# BitReceptor.net
KiCad netlist of a schematic drawn in EAGLE
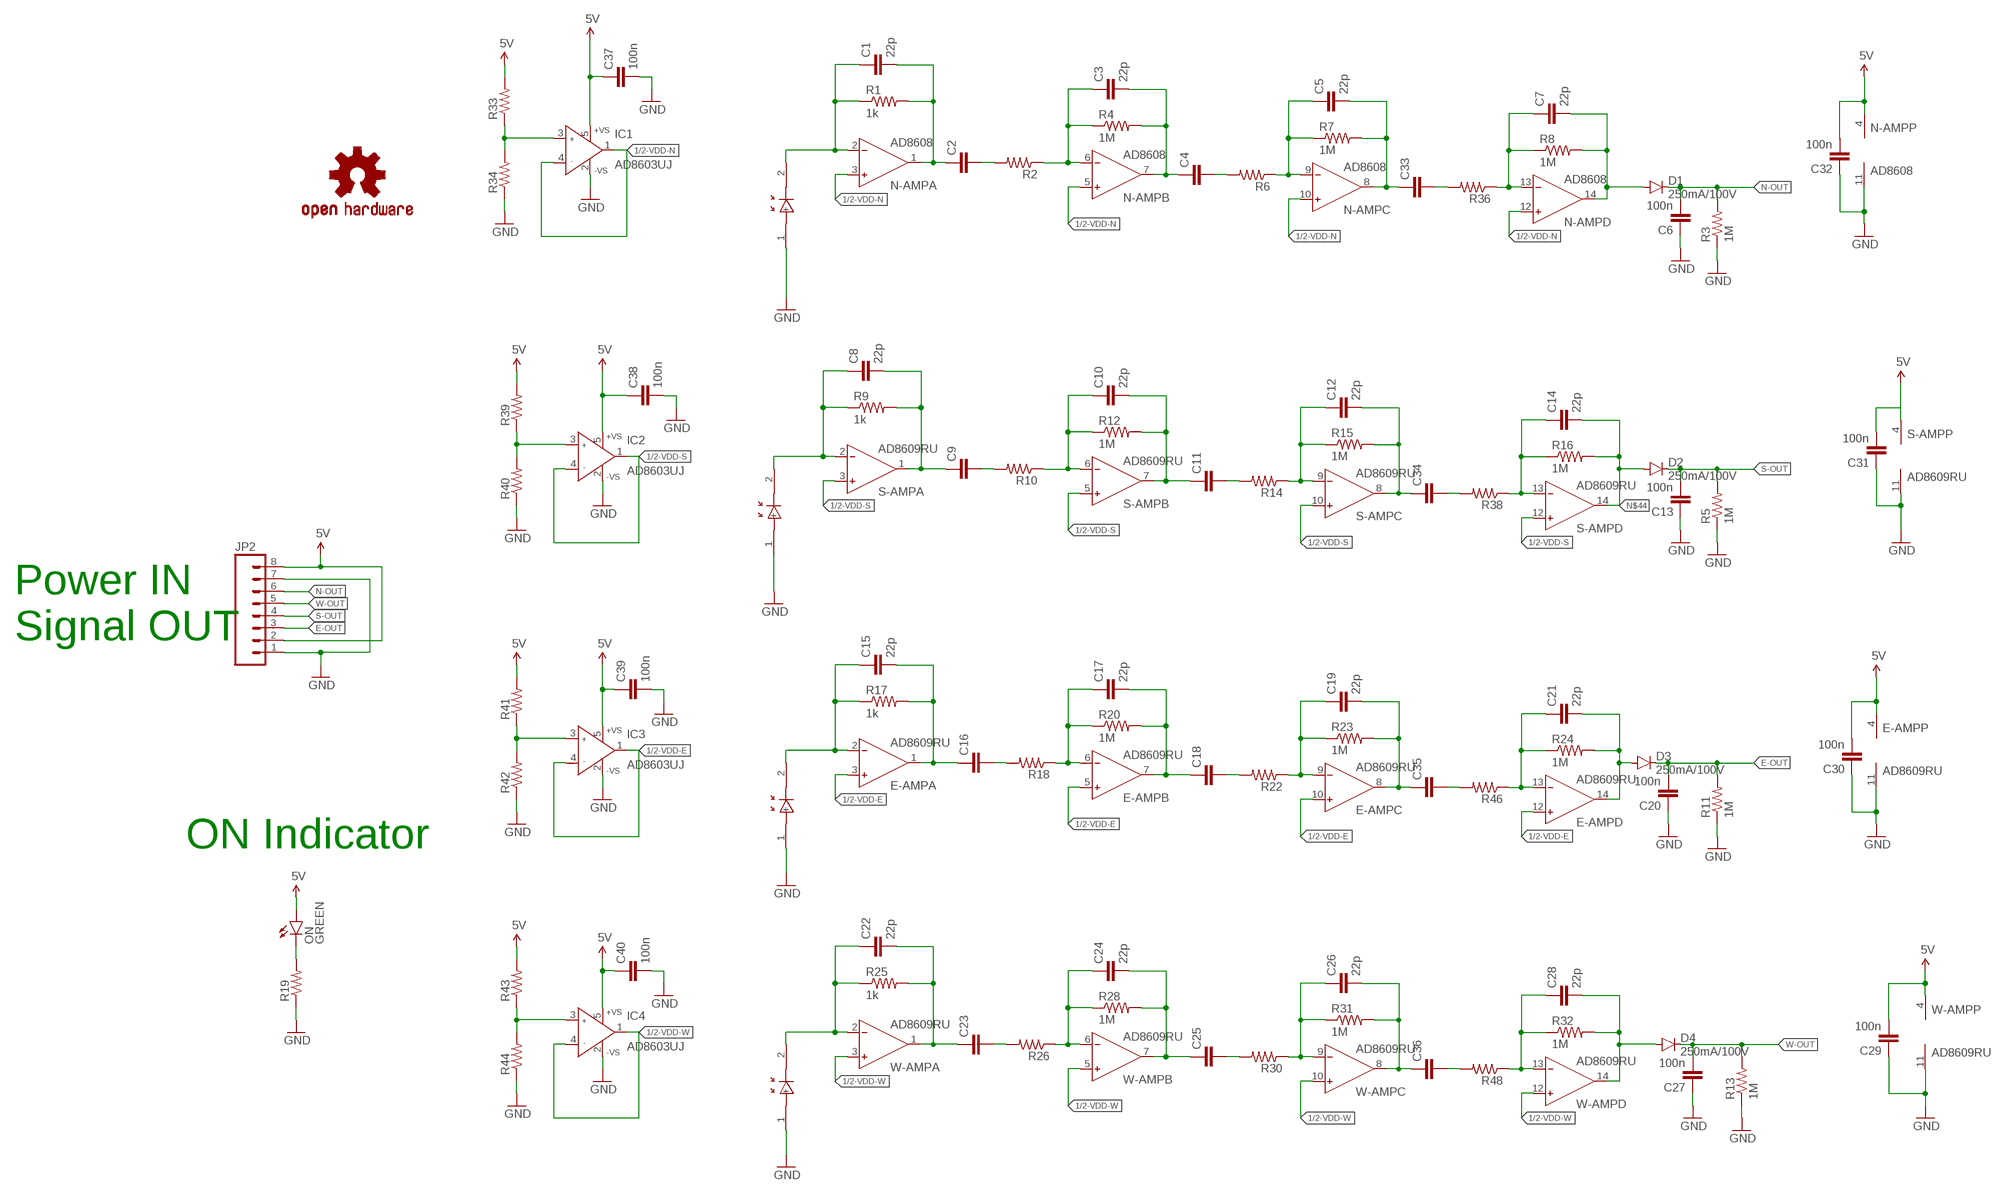
[diagram p0: schematic, sheet 1]

(export (version "E")
  (design (tool "Eeschema 10.0.6"))
  (components
    (comp (ref "C1")
      (value "22p")
      (footprint "eagle-import:C0402")
      (libsource (lib "eagle-import") (part "C-EUC0402"))
    )
    (comp (ref "C2")
      (value "C-EUC0402")
      (footprint "eagle-import:C0402")
      (libsource (lib "eagle-import") (part "C-EUC0402"))
    )
    (comp (ref "C3")
      (value "22p")
      (footprint "eagle-import:C0402")
      (libsource (lib "eagle-import") (part "C-EUC0402"))
    )
    (comp (ref "C4")
      (value "C-EUC0402")
      (footprint "eagle-import:C0402")
      (libsource (lib "eagle-import") (part "C-EUC0402"))
    )
    (comp (ref "C5")
      (value "22p")
      (footprint "eagle-import:C0402")
      (libsource (lib "eagle-import") (part "C-EUC0402"))
    )
    (comp (ref "C6")
      (value "100n")
      (footprint "eagle-import:C0402")
      (libsource (lib "eagle-import") (part "C-EUC0402"))
    )
    (comp (ref "C7")
      (value "22p")
      (footprint "eagle-import:C0402")
      (libsource (lib "eagle-import") (part "C-EUC0402"))
    )
    (comp (ref "C8")
      (value "22p")
      (footprint "eagle-import:C0402")
      (libsource (lib "eagle-import") (part "C-EUC0402"))
    )
    (comp (ref "C9")
      (value "C-EUC0402")
      (footprint "eagle-import:C0402")
      (libsource (lib "eagle-import") (part "C-EUC0402"))
    )
    (comp (ref "C10")
      (value "22p")
      (footprint "eagle-import:C0402")
      (libsource (lib "eagle-import") (part "C-EUC0402"))
    )
    (comp (ref "C11")
      (value "C-EUC0402")
      (footprint "eagle-import:C0402")
      (libsource (lib "eagle-import") (part "C-EUC0402"))
    )
    (comp (ref "C12")
      (value "22p")
      (footprint "eagle-import:C0402")
      (libsource (lib "eagle-import") (part "C-EUC0402"))
    )
    (comp (ref "C13")
      (value "100n")
      (footprint "eagle-import:C0402")
      (libsource (lib "eagle-import") (part "C-EUC0402"))
    )
    (comp (ref "C14")
      (value "22p")
      (footprint "eagle-import:C0402")
      (libsource (lib "eagle-import") (part "C-EUC0402"))
    )
    (comp (ref "C15")
      (value "22p")
      (footprint "eagle-import:C0402")
      (libsource (lib "eagle-import") (part "C-EUC0402"))
    )
    (comp (ref "C16")
      (value "C-EUC0402")
      (footprint "eagle-import:C0402")
      (libsource (lib "eagle-import") (part "C-EUC0402"))
    )
    (comp (ref "C17")
      (value "22p")
      (footprint "eagle-import:C0402")
      (libsource (lib "eagle-import") (part "C-EUC0402"))
    )
    (comp (ref "C18")
      (value "C-EUC0402")
      (footprint "eagle-import:C0402")
      (libsource (lib "eagle-import") (part "C-EUC0402"))
    )
    (comp (ref "C19")
      (value "22p")
      (footprint "eagle-import:C0402")
      (libsource (lib "eagle-import") (part "C-EUC0402"))
    )
    (comp (ref "C20")
      (value "100n")
      (footprint "eagle-import:C0402")
      (libsource (lib "eagle-import") (part "C-EUC0402"))
    )
    (comp (ref "C21")
      (value "22p")
      (footprint "eagle-import:C0402")
      (libsource (lib "eagle-import") (part "C-EUC0402"))
    )
    (comp (ref "C22")
      (value "22p")
      (footprint "eagle-import:C0402")
      (libsource (lib "eagle-import") (part "C-EUC0402"))
    )
    (comp (ref "C23")
      (value "C-EUC0402")
      (footprint "eagle-import:C0402")
      (libsource (lib "eagle-import") (part "C-EUC0402"))
    )
    (comp (ref "C24")
      (value "22p")
      (footprint "eagle-import:C0402")
      (libsource (lib "eagle-import") (part "C-EUC0402"))
    )
    (comp (ref "C25")
      (value "C-EUC0402")
      (footprint "eagle-import:C0402")
      (libsource (lib "eagle-import") (part "C-EUC0402"))
    )
    (comp (ref "C26")
      (value "22p")
      (footprint "eagle-import:C0402")
      (libsource (lib "eagle-import") (part "C-EUC0402"))
    )
    (comp (ref "C27")
      (value "100n")
      (footprint "eagle-import:C0402")
      (libsource (lib "eagle-import") (part "C-EUC0402"))
    )
    (comp (ref "C28")
      (value "22p")
      (footprint "eagle-import:C0402")
      (libsource (lib "eagle-import") (part "C-EUC0402"))
    )
    (comp (ref "C29")
      (value "100n")
      (footprint "eagle-import:C0402")
      (libsource (lib "eagle-import") (part "C-EUC0402"))
    )
    (comp (ref "C30")
      (value "100n")
      (footprint "eagle-import:C0402")
      (libsource (lib "eagle-import") (part "C-EUC0402"))
    )
    (comp (ref "C31")
      (value "100n")
      (footprint "eagle-import:C0402")
      (libsource (lib "eagle-import") (part "C-EUC0402"))
    )
    (comp (ref "C32")
      (value "100n")
      (footprint "eagle-import:C0402")
      (libsource (lib "eagle-import") (part "C-EUC0402"))
    )
    (comp (ref "C33")
      (value "C-EUC0402")
      (footprint "eagle-import:C0402")
      (libsource (lib "eagle-import") (part "C-EUC0402"))
    )
    (comp (ref "C34")
      (value "C-EUC0402")
      (footprint "eagle-import:C0402")
      (libsource (lib "eagle-import") (part "C-EUC0402"))
    )
    (comp (ref "C35")
      (value "C-EUC0402")
      (footprint "eagle-import:C0402")
      (libsource (lib "eagle-import") (part "C-EUC0402"))
    )
    (comp (ref "C36")
      (value "C-EUC0402")
      (footprint "eagle-import:C0402")
      (libsource (lib "eagle-import") (part "C-EUC0402"))
    )
    (comp (ref "C37")
      (value "100n")
      (footprint "eagle-import:C0402")
      (libsource (lib "eagle-import") (part "C-EUC0402"))
    )
    (comp (ref "C38")
      (value "100n")
      (footprint "eagle-import:C0402")
      (libsource (lib "eagle-import") (part "C-EUC0402"))
    )
    (comp (ref "C39")
      (value "100n")
      (footprint "eagle-import:C0402")
      (libsource (lib "eagle-import") (part "C-EUC0402"))
    )
    (comp (ref "C40")
      (value "100n")
      (footprint "eagle-import:C0402")
      (libsource (lib "eagle-import") (part "C-EUC0402"))
    )
    (comp (ref "D1")
      (value "250mA/100V")
      (footprint "eagle-import:SOD-323")
      (libsource (lib "eagle-import") (part "DIODEBAS16"))
    )
    (comp (ref "D2")
      (value "250mA/100V")
      (footprint "eagle-import:SOD-323")
      (libsource (lib "eagle-import") (part "DIODEBAS16"))
    )
    (comp (ref "D3")
      (value "250mA/100V")
      (footprint "eagle-import:SOD-323")
      (libsource (lib "eagle-import") (part "DIODEBAS16"))
    )
    (comp (ref "D4")
      (value "250mA/100V")
      (footprint "eagle-import:SOD-323")
      (libsource (lib "eagle-import") (part "DIODEBAS16"))
    )
    (comp (ref "E-AMP")
      (value "AD8609RU")
      (footprint "eagle-import:TSSOP14")
      (fields (field (name "MF") "ALTERA CORPORATION") (field (name "MPN") "AD8609ARUZ"))
      (libsource (lib "eagle-import") (part "AD8609RU"))
    )
    (comp (ref "E-PD1")
      (value "BPW46")
      (footprint "eagle-import:PIN-PHOTODIODE")
      (libsource (lib "eagle-import") (part "BPW46"))
    )
    (comp (ref "IC1")
      (value "AD8603UJ")
      (footprint "eagle-import:SOT23-5")
      (fields (field (name "MF") "ALTERA CORPORATION") (field (name "MPN") "AD8603AUJZ-REEL7"))
      (libsource (lib "eagle-import") (part "AD8603UJ"))
    )
    (comp (ref "IC2")
      (value "AD8603UJ")
      (footprint "eagle-import:SOT23-5")
      (fields (field (name "MF") "ALTERA CORPORATION") (field (name "MPN") "AD8603AUJZ-REEL7"))
      (libsource (lib "eagle-import") (part "AD8603UJ"))
    )
    (comp (ref "IC3")
      (value "AD8603UJ")
      (footprint "eagle-import:SOT23-5")
      (fields (field (name "MF") "ALTERA CORPORATION") (field (name "MPN") "AD8603AUJZ-REEL7"))
      (libsource (lib "eagle-import") (part "AD8603UJ"))
    )
    (comp (ref "IC4")
      (value "AD8603UJ")
      (footprint "eagle-import:SOT23-5")
      (fields (field (name "MF") "ALTERA CORPORATION") (field (name "MPN") "AD8603AUJZ-REEL7"))
      (libsource (lib "eagle-import") (part "AD8603UJ"))
    )
    (comp (ref "JP2")
      (value "M08NO_SILK")
      (footprint "eagle-import:1X08_PIN1_NO_SILK")
      (libsource (lib "eagle-import") (part "M08NO_SILK"))
    )
    (comp (ref "LOGO1")
      (value "OSHW-LOGOS")
      (footprint "eagle-import:OSHW-LOGO-S")
      (libsource (lib "eagle-import") (part "OSHW-LOGOS"))
    )
    (comp (ref "N-AMP")
      (value "AD8608")
      (footprint "eagle-import:TSSOP14")
      (fields (field (name "MF") "ALTERA CORPORATION") (field (name "MPN") "AD8609ARUZ"))
      (libsource (lib "eagle-import") (part "AD8609RU"))
    )
    (comp (ref "N-PD1")
      (value "BPW46")
      (footprint "eagle-import:PIN-PHOTODIODE")
      (libsource (lib "eagle-import") (part "BPW46"))
    )
    (comp (ref "ON")
      (value "GREEN")
      (footprint "eagle-import:LED-0603")
      (libsource (lib "eagle-import") (part "LED-GREEN0603"))
    )
    (comp (ref "R1")
      (value "1k")
      (footprint "eagle-import:R0402")
      (libsource (lib "eagle-import") (part "R-US_R0402"))
    )
    (comp (ref "R2")
      (value "R-US_R0402")
      (footprint "eagle-import:R0402")
      (libsource (lib "eagle-import") (part "R-US_R0402"))
    )
    (comp (ref "R3")
      (value "1M")
      (footprint "eagle-import:R0402")
      (libsource (lib "eagle-import") (part "R-US_R0402"))
    )
    (comp (ref "R4")
      (value "1M")
      (footprint "eagle-import:R0402")
      (libsource (lib "eagle-import") (part "R-US_R0402"))
    )
    (comp (ref "R5")
      (value "1M")
      (footprint "eagle-import:R0402")
      (libsource (lib "eagle-import") (part "R-US_R0402"))
    )
    (comp (ref "R6")
      (value "R-US_R0402")
      (footprint "eagle-import:R0402")
      (libsource (lib "eagle-import") (part "R-US_R0402"))
    )
    (comp (ref "R7")
      (value "1M")
      (footprint "eagle-import:R0402")
      (libsource (lib "eagle-import") (part "R-US_R0402"))
    )
    (comp (ref "R8")
      (value "1M")
      (footprint "eagle-import:R0402")
      (libsource (lib "eagle-import") (part "R-US_R0402"))
    )
    (comp (ref "R9")
      (value "1k")
      (footprint "eagle-import:R0402")
      (libsource (lib "eagle-import") (part "R-US_R0402"))
    )
    (comp (ref "R10")
      (value "R-US_R0402")
      (footprint "eagle-import:R0402")
      (libsource (lib "eagle-import") (part "R-US_R0402"))
    )
    (comp (ref "R11")
      (value "1M")
      (footprint "eagle-import:R0402")
      (libsource (lib "eagle-import") (part "R-US_R0402"))
    )
    (comp (ref "R12")
      (value "1M")
      (footprint "eagle-import:R0402")
      (libsource (lib "eagle-import") (part "R-US_R0402"))
    )
    (comp (ref "R13")
      (value "1M")
      (footprint "eagle-import:R0402")
      (libsource (lib "eagle-import") (part "R-US_R0402"))
    )
    (comp (ref "R14")
      (value "R-US_R0402")
      (footprint "eagle-import:R0402")
      (libsource (lib "eagle-import") (part "R-US_R0402"))
    )
    (comp (ref "R15")
      (value "1M")
      (footprint "eagle-import:R0402")
      (libsource (lib "eagle-import") (part "R-US_R0402"))
    )
    (comp (ref "R16")
      (value "1M")
      (footprint "eagle-import:R0402")
      (libsource (lib "eagle-import") (part "R-US_R0402"))
    )
    (comp (ref "R17")
      (value "1k")
      (footprint "eagle-import:R0402")
      (libsource (lib "eagle-import") (part "R-US_R0402"))
    )
    (comp (ref "R18")
      (value "R-US_R0402")
      (footprint "eagle-import:R0402")
      (libsource (lib "eagle-import") (part "R-US_R0402"))
    )
    (comp (ref "R19")
      (value "R-US_R0402")
      (footprint "eagle-import:R0402")
      (libsource (lib "eagle-import") (part "R-US_R0402"))
    )
    (comp (ref "R20")
      (value "1M")
      (footprint "eagle-import:R0402")
      (libsource (lib "eagle-import") (part "R-US_R0402"))
    )
    (comp (ref "R22")
      (value "R-US_R0402")
      (footprint "eagle-import:R0402")
      (libsource (lib "eagle-import") (part "R-US_R0402"))
    )
    (comp (ref "R23")
      (value "1M")
      (footprint "eagle-import:R0402")
      (libsource (lib "eagle-import") (part "R-US_R0402"))
    )
    (comp (ref "R24")
      (value "1M")
      (footprint "eagle-import:R0402")
      (libsource (lib "eagle-import") (part "R-US_R0402"))
    )
    (comp (ref "R25")
      (value "1k")
      (footprint "eagle-import:R0402")
      (libsource (lib "eagle-import") (part "R-US_R0402"))
    )
    (comp (ref "R26")
      (value "R-US_R0402")
      (footprint "eagle-import:R0402")
      (libsource (lib "eagle-import") (part "R-US_R0402"))
    )
    (comp (ref "R28")
      (value "1M")
      (footprint "eagle-import:R0402")
      (libsource (lib "eagle-import") (part "R-US_R0402"))
    )
    (comp (ref "R30")
      (value "R-US_R0402")
      (footprint "eagle-import:R0402")
      (libsource (lib "eagle-import") (part "R-US_R0402"))
    )
    (comp (ref "R31")
      (value "1M")
      (footprint "eagle-import:R0402")
      (libsource (lib "eagle-import") (part "R-US_R0402"))
    )
    (comp (ref "R32")
      (value "1M")
      (footprint "eagle-import:R0402")
      (libsource (lib "eagle-import") (part "R-US_R0402"))
    )
    (comp (ref "R33")
      (value "R-US_R0402")
      (footprint "eagle-import:R0402")
      (libsource (lib "eagle-import") (part "R-US_R0402"))
    )
    (comp (ref "R34")
      (value "R-US_R0402")
      (footprint "eagle-import:R0402")
      (libsource (lib "eagle-import") (part "R-US_R0402"))
    )
    (comp (ref "R36")
      (value "R-US_R0402")
      (footprint "eagle-import:R0402")
      (libsource (lib "eagle-import") (part "R-US_R0402"))
    )
    (comp (ref "R38")
      (value "R-US_R0402")
      (footprint "eagle-import:R0402")
      (libsource (lib "eagle-import") (part "R-US_R0402"))
    )
    (comp (ref "R39")
      (value "R-US_R0402")
      (footprint "eagle-import:R0402")
      (libsource (lib "eagle-import") (part "R-US_R0402"))
    )
    (comp (ref "R40")
      (value "R-US_R0402")
      (footprint "eagle-import:R0402")
      (libsource (lib "eagle-import") (part "R-US_R0402"))
    )
    (comp (ref "R41")
      (value "R-US_R0402")
      (footprint "eagle-import:R0402")
      (libsource (lib "eagle-import") (part "R-US_R0402"))
    )
    (comp (ref "R42")
      (value "R-US_R0402")
      (footprint "eagle-import:R0402")
      (libsource (lib "eagle-import") (part "R-US_R0402"))
    )
    (comp (ref "R43")
      (value "R-US_R0402")
      (footprint "eagle-import:R0402")
      (libsource (lib "eagle-import") (part "R-US_R0402"))
    )
    (comp (ref "R44")
      (value "R-US_R0402")
      (footprint "eagle-import:R0402")
      (libsource (lib "eagle-import") (part "R-US_R0402"))
    )
    (comp (ref "R46")
      (value "R-US_R0402")
      (footprint "eagle-import:R0402")
      (libsource (lib "eagle-import") (part "R-US_R0402"))
    )
    (comp (ref "R48")
      (value "R-US_R0402")
      (footprint "eagle-import:R0402")
      (libsource (lib "eagle-import") (part "R-US_R0402"))
    )
    (comp (ref "S-AMP")
      (value "AD8609RU")
      (footprint "eagle-import:TSSOP14")
      (fields (field (name "MF") "ALTERA CORPORATION") (field (name "MPN") "AD8609ARUZ"))
      (libsource (lib "eagle-import") (part "AD8609RU"))
    )
    (comp (ref "S-PD1")
      (value "BPW46")
      (footprint "eagle-import:PIN-PHOTODIODE")
      (libsource (lib "eagle-import") (part "BPW46"))
    )
    (comp (ref "W-AMP")
      (value "AD8609RU")
      (footprint "eagle-import:TSSOP14")
      (fields (field (name "MF") "ALTERA CORPORATION") (field (name "MPN") "AD8609ARUZ"))
      (libsource (lib "eagle-import") (part "AD8609RU"))
    )
    (comp (ref "W-PD1")
      (value "BPW46")
      (footprint "eagle-import:PIN-PHOTODIODE")
      (libsource (lib "eagle-import") (part "BPW46"))
    )
  )
  (nets
    (net (code "1") (name "1{slash}2-VDD-E") (class "Default")
      (node (ref "E-AMP") (pin "10") (pinfunction "IN+_10") (pintype "input"))
      (node (ref "E-AMP") (pin "12") (pinfunction "IN+_12") (pintype "input"))
      (node (ref "E-AMP") (pin "3") (pinfunction "IN+_3") (pintype "input"))
      (node (ref "E-AMP") (pin "5") (pinfunction "IN+_5") (pintype "input"))
      (node (ref "IC3") (pin "1") (pinfunction "OUT_1") (pintype "output"))
      (node (ref "IC3") (pin "4") (pinfunction "IN-_4") (pintype "input"))
    )
    (net (code "2") (name "1{slash}2-VDD-N") (class "Default")
      (node (ref "IC1") (pin "1") (pinfunction "OUT_1") (pintype "output"))
      (node (ref "IC1") (pin "4") (pinfunction "IN-_4") (pintype "input"))
      (node (ref "N-AMP") (pin "10") (pinfunction "IN+_10") (pintype "input"))
      (node (ref "N-AMP") (pin "12") (pinfunction "IN+_12") (pintype "input"))
      (node (ref "N-AMP") (pin "3") (pinfunction "IN+_3") (pintype "input"))
      (node (ref "N-AMP") (pin "5") (pinfunction "IN+_5") (pintype "input"))
    )
    (net (code "3") (name "1{slash}2-VDD-S") (class "Default")
      (node (ref "IC2") (pin "1") (pinfunction "OUT_1") (pintype "output"))
      (node (ref "IC2") (pin "4") (pinfunction "IN-_4") (pintype "input"))
      (node (ref "S-AMP") (pin "10") (pinfunction "IN+_10") (pintype "input"))
      (node (ref "S-AMP") (pin "12") (pinfunction "IN+_12") (pintype "input"))
      (node (ref "S-AMP") (pin "3") (pinfunction "IN+_3") (pintype "input"))
      (node (ref "S-AMP") (pin "5") (pinfunction "IN+_5") (pintype "input"))
    )
    (net (code "4") (name "1{slash}2-VDD-W") (class "Default")
      (node (ref "IC4") (pin "1") (pinfunction "OUT_1") (pintype "output"))
      (node (ref "IC4") (pin "4") (pinfunction "IN-_4") (pintype "input"))
      (node (ref "W-AMP") (pin "10") (pinfunction "IN+_10") (pintype "input"))
      (node (ref "W-AMP") (pin "12") (pinfunction "IN+_12") (pintype "input"))
      (node (ref "W-AMP") (pin "3") (pinfunction "IN+_3") (pintype "input"))
      (node (ref "W-AMP") (pin "5") (pinfunction "IN+_5") (pintype "input"))
    )
    (net (code "5") (name "5V") (class "Default")
      (node (ref "C29") (pin "2") (pinfunction "2_2") (pintype "passive"))
      (node (ref "C30") (pin "2") (pinfunction "2_2") (pintype "passive"))
      (node (ref "C31") (pin "2") (pinfunction "2_2") (pintype "passive"))
      (node (ref "C32") (pin "2") (pinfunction "2_2") (pintype "passive"))
      (node (ref "C37") (pin "1") (pinfunction "1_1") (pintype "passive"))
      (node (ref "C38") (pin "1") (pinfunction "1_1") (pintype "passive"))
      (node (ref "C39") (pin "1") (pinfunction "1_1") (pintype "passive"))
      (node (ref "C40") (pin "1") (pinfunction "1_1") (pintype "passive"))
      (node (ref "E-AMP") (pin "4") (pinfunction "V+_4") (pintype "power_in"))
      (node (ref "IC1") (pin "5") (pinfunction "+VS_5") (pintype "input"))
      (node (ref "IC2") (pin "5") (pinfunction "+VS_5") (pintype "input"))
      (node (ref "IC3") (pin "5") (pinfunction "+VS_5") (pintype "input"))
      (node (ref "IC4") (pin "5") (pinfunction "+VS_5") (pintype "input"))
      (node (ref "JP2") (pin "2") (pinfunction "2_2") (pintype "passive"))
      (node (ref "JP2") (pin "8") (pinfunction "8_8") (pintype "passive"))
      (node (ref "N-AMP") (pin "4") (pinfunction "V+_4") (pintype "power_in"))
      (node (ref "ON") (pin "A") (pinfunction "A_A") (pintype "passive"))
      (node (ref "R33") (pin "2") (pinfunction "2_2") (pintype "passive"))
      (node (ref "R39") (pin "2") (pinfunction "2_2") (pintype "passive"))
      (node (ref "R41") (pin "2") (pinfunction "2_2") (pintype "passive"))
      (node (ref "R43") (pin "2") (pinfunction "2_2") (pintype "passive"))
      (node (ref "S-AMP") (pin "4") (pinfunction "V+_4") (pintype "power_in"))
      (node (ref "W-AMP") (pin "4") (pinfunction "V+_4") (pintype "power_in"))
    )
    (net (code "6") (name "E-OUT") (class "Default")
      (node (ref "C20") (pin "2") (pinfunction "2_2") (pintype "passive"))
      (node (ref "D3") (pin "C") (pinfunction "C_C") (pintype "passive"))
      (node (ref "JP2") (pin "3") (pinfunction "3_3") (pintype "passive"))
      (node (ref "R11") (pin "2") (pinfunction "2_2") (pintype "passive"))
    )
    (net (code "7") (name "GND") (class "Default")
      (node (ref "C13") (pin "1") (pinfunction "1_1") (pintype "passive"))
      (node (ref "C20") (pin "1") (pinfunction "1_1") (pintype "passive"))
      (node (ref "C27") (pin "1") (pinfunction "1_1") (pintype "passive"))
      (node (ref "C29") (pin "1") (pinfunction "1_1") (pintype "passive"))
      (node (ref "C30") (pin "1") (pinfunction "1_1") (pintype "passive"))
      (node (ref "C31") (pin "1") (pinfunction "1_1") (pintype "passive"))
      (node (ref "C32") (pin "1") (pinfunction "1_1") (pintype "passive"))
      (node (ref "C37") (pin "2") (pinfunction "2_2") (pintype "passive"))
      (node (ref "C38") (pin "2") (pinfunction "2_2") (pintype "passive"))
      (node (ref "C39") (pin "2") (pinfunction "2_2") (pintype "passive"))
      (node (ref "C40") (pin "2") (pinfunction "2_2") (pintype "passive"))
      (node (ref "C6") (pin "1") (pinfunction "1_1") (pintype "passive"))
      (node (ref "E-AMP") (pin "11") (pinfunction "V-_11") (pintype "power_in"))
      (node (ref "E-PD1") (pin "1") (pinfunction "+_1") (pintype "bidirectional"))
      (node (ref "IC1") (pin "2") (pinfunction "-VS_2") (pintype "input"))
      (node (ref "IC2") (pin "2") (pinfunction "-VS_2") (pintype "input"))
      (node (ref "IC3") (pin "2") (pinfunction "-VS_2") (pintype "input"))
      (node (ref "IC4") (pin "2") (pinfunction "-VS_2") (pintype "input"))
      (node (ref "JP2") (pin "1") (pinfunction "1_1") (pintype "passive"))
      (node (ref "JP2") (pin "7") (pinfunction "7_7") (pintype "passive"))
      (node (ref "N-AMP") (pin "11") (pinfunction "V-_11") (pintype "power_in"))
      (node (ref "N-PD1") (pin "1") (pinfunction "+_1") (pintype "bidirectional"))
      (node (ref "R11") (pin "1") (pinfunction "1_1") (pintype "passive"))
      (node (ref "R13") (pin "1") (pinfunction "1_1") (pintype "passive"))
      (node (ref "R19") (pin "1") (pinfunction "1_1") (pintype "passive"))
      (node (ref "R3") (pin "1") (pinfunction "1_1") (pintype "passive"))
      (node (ref "R34") (pin "1") (pinfunction "1_1") (pintype "passive"))
      (node (ref "R40") (pin "1") (pinfunction "1_1") (pintype "passive"))
      (node (ref "R42") (pin "1") (pinfunction "1_1") (pintype "passive"))
      (node (ref "R44") (pin "1") (pinfunction "1_1") (pintype "passive"))
      (node (ref "R5") (pin "1") (pinfunction "1_1") (pintype "passive"))
      (node (ref "S-AMP") (pin "11") (pinfunction "V-_11") (pintype "power_in"))
      (node (ref "S-PD1") (pin "1") (pinfunction "+_1") (pintype "bidirectional"))
      (node (ref "W-AMP") (pin "11") (pinfunction "V-_11") (pintype "power_in"))
      (node (ref "W-PD1") (pin "1") (pinfunction "+_1") (pintype "bidirectional"))
    )
    (net (code "8") (name "N$44") (class "Default")
      (node (ref "C14") (pin "2") (pinfunction "2_2") (pintype "passive"))
      (node (ref "D2") (pin "A") (pinfunction "A_A") (pintype "passive"))
      (node (ref "R16") (pin "2") (pinfunction "2_2") (pintype "passive"))
      (node (ref "S-AMP") (pin "14") (pinfunction "OUT_14") (pintype "output"))
    )
    (net (code "9") (name "N-OUT") (class "Default")
      (node (ref "C6") (pin "2") (pinfunction "2_2") (pintype "passive"))
      (node (ref "D1") (pin "C") (pinfunction "C_C") (pintype "passive"))
      (node (ref "JP2") (pin "6") (pinfunction "6_6") (pintype "passive"))
      (node (ref "R3") (pin "2") (pinfunction "2_2") (pintype "passive"))
    )
    (net (code "10") (name "Net-(C2-Pad2)") (class "Default")
      (node (ref "C2") (pin "2") (pinfunction "2_2") (pintype "passive"))
      (node (ref "R2") (pin "2") (pinfunction "2_2") (pintype "passive"))
    )
    (net (code "11") (name "Net-(C4-Pad2)") (class "Default")
      (node (ref "C4") (pin "2") (pinfunction "2_2") (pintype "passive"))
      (node (ref "R6") (pin "2") (pinfunction "2_2") (pintype "passive"))
    )
    (net (code "12") (name "Net-(C9-Pad2)") (class "Default")
      (node (ref "C9") (pin "2") (pinfunction "2_2") (pintype "passive"))
      (node (ref "R10") (pin "2") (pinfunction "2_2") (pintype "passive"))
    )
    (net (code "13") (name "Net-(C11-Pad2)") (class "Default")
      (node (ref "C11") (pin "2") (pinfunction "2_2") (pintype "passive"))
      (node (ref "R14") (pin "2") (pinfunction "2_2") (pintype "passive"))
    )
    (net (code "14") (name "Net-(C16-Pad2)") (class "Default")
      (node (ref "C16") (pin "2") (pinfunction "2_2") (pintype "passive"))
      (node (ref "R18") (pin "2") (pinfunction "2_2") (pintype "passive"))
    )
    (net (code "15") (name "Net-(C18-Pad2)") (class "Default")
      (node (ref "C18") (pin "2") (pinfunction "2_2") (pintype "passive"))
      (node (ref "R22") (pin "2") (pinfunction "2_2") (pintype "passive"))
    )
    (net (code "16") (name "Net-(C23-Pad2)") (class "Default")
      (node (ref "C23") (pin "2") (pinfunction "2_2") (pintype "passive"))
      (node (ref "R26") (pin "2") (pinfunction "2_2") (pintype "passive"))
    )
    (net (code "17") (name "Net-(C25-Pad2)") (class "Default")
      (node (ref "C25") (pin "2") (pinfunction "2_2") (pintype "passive"))
      (node (ref "R30") (pin "2") (pinfunction "2_2") (pintype "passive"))
    )
    (net (code "18") (name "Net-(C33-Pad2)") (class "Default")
      (node (ref "C33") (pin "2") (pinfunction "2_2") (pintype "passive"))
      (node (ref "R36") (pin "2") (pinfunction "2_2") (pintype "passive"))
    )
    (net (code "19") (name "Net-(C34-Pad2)") (class "Default")
      (node (ref "C34") (pin "2") (pinfunction "2_2") (pintype "passive"))
      (node (ref "R38") (pin "2") (pinfunction "2_2") (pintype "passive"))
    )
    (net (code "20") (name "Net-(C35-Pad2)") (class "Default")
      (node (ref "C35") (pin "2") (pinfunction "2_2") (pintype "passive"))
      (node (ref "R46") (pin "2") (pinfunction "2_2") (pintype "passive"))
    )
    (net (code "21") (name "Net-(C36-Pad2)") (class "Default")
      (node (ref "C36") (pin "2") (pinfunction "2_2") (pintype "passive"))
      (node (ref "R48") (pin "2") (pinfunction "2_2") (pintype "passive"))
    )
    (net (code "22") (name "Net-(E-AMPA-IN-)") (class "Default")
      (node (ref "C15") (pin "1") (pinfunction "1_1") (pintype "passive"))
      (node (ref "E-AMP") (pin "2") (pinfunction "IN-_2") (pintype "input"))
      (node (ref "E-PD1") (pin "2") (pinfunction "-_2") (pintype "bidirectional"))
      (node (ref "R17") (pin "1") (pinfunction "1_1") (pintype "passive"))
    )
    (net (code "23") (name "Net-(E-AMPA-OUT)") (class "Default")
      (node (ref "C15") (pin "2") (pinfunction "2_2") (pintype "passive"))
      (node (ref "C16") (pin "1") (pinfunction "1_1") (pintype "passive"))
      (node (ref "E-AMP") (pin "1") (pinfunction "OUT_1") (pintype "output"))
      (node (ref "R17") (pin "2") (pinfunction "2_2") (pintype "passive"))
    )
    (net (code "24") (name "Net-(E-AMPB-IN-)") (class "Default")
      (node (ref "C17") (pin "1") (pinfunction "1_1") (pintype "passive"))
      (node (ref "E-AMP") (pin "6") (pinfunction "IN-_6") (pintype "input"))
      (node (ref "R18") (pin "1") (pinfunction "1_1") (pintype "passive"))
      (node (ref "R20") (pin "1") (pinfunction "1_1") (pintype "passive"))
    )
    (net (code "25") (name "Net-(E-AMPB-OUT)") (class "Default")
      (node (ref "C17") (pin "2") (pinfunction "2_2") (pintype "passive"))
      (node (ref "C18") (pin "1") (pinfunction "1_1") (pintype "passive"))
      (node (ref "E-AMP") (pin "7") (pinfunction "OUT_7") (pintype "output"))
      (node (ref "R20") (pin "2") (pinfunction "2_2") (pintype "passive"))
    )
    (net (code "26") (name "Net-(E-AMPC-IN-)") (class "Default")
      (node (ref "C19") (pin "1") (pinfunction "1_1") (pintype "passive"))
      (node (ref "E-AMP") (pin "9") (pinfunction "IN-_9") (pintype "input"))
      (node (ref "R22") (pin "1") (pinfunction "1_1") (pintype "passive"))
      (node (ref "R23") (pin "1") (pinfunction "1_1") (pintype "passive"))
    )
    (net (code "27") (name "Net-(E-AMPC-OUT)") (class "Default")
      (node (ref "C19") (pin "2") (pinfunction "2_2") (pintype "passive"))
      (node (ref "C35") (pin "1") (pinfunction "1_1") (pintype "passive"))
      (node (ref "E-AMP") (pin "8") (pinfunction "OUT_8") (pintype "output"))
      (node (ref "R23") (pin "2") (pinfunction "2_2") (pintype "passive"))
    )
    (net (code "28") (name "Net-(E-AMPD-IN-)") (class "Default")
      (node (ref "C21") (pin "1") (pinfunction "1_1") (pintype "passive"))
      (node (ref "E-AMP") (pin "13") (pinfunction "IN-_13") (pintype "input"))
      (node (ref "R24") (pin "1") (pinfunction "1_1") (pintype "passive"))
      (node (ref "R46") (pin "1") (pinfunction "1_1") (pintype "passive"))
    )
    (net (code "29") (name "Net-(E-AMPD-OUT)") (class "Default")
      (node (ref "C21") (pin "2") (pinfunction "2_2") (pintype "passive"))
      (node (ref "D3") (pin "A") (pinfunction "A_A") (pintype "passive"))
      (node (ref "E-AMP") (pin "14") (pinfunction "OUT_14") (pintype "output"))
      (node (ref "R24") (pin "2") (pinfunction "2_2") (pintype "passive"))
    )
    (net (code "30") (name "Net-(IC1-IN+)") (class "Default")
      (node (ref "IC1") (pin "3") (pinfunction "IN+_3") (pintype "input"))
      (node (ref "R33") (pin "1") (pinfunction "1_1") (pintype "passive"))
      (node (ref "R34") (pin "2") (pinfunction "2_2") (pintype "passive"))
    )
    (net (code "31") (name "Net-(IC2-IN+)") (class "Default")
      (node (ref "IC2") (pin "3") (pinfunction "IN+_3") (pintype "input"))
      (node (ref "R39") (pin "1") (pinfunction "1_1") (pintype "passive"))
      (node (ref "R40") (pin "2") (pinfunction "2_2") (pintype "passive"))
    )
    (net (code "32") (name "Net-(IC3-IN+)") (class "Default")
      (node (ref "IC3") (pin "3") (pinfunction "IN+_3") (pintype "input"))
      (node (ref "R41") (pin "1") (pinfunction "1_1") (pintype "passive"))
      (node (ref "R42") (pin "2") (pinfunction "2_2") (pintype "passive"))
    )
    (net (code "33") (name "Net-(IC4-IN+)") (class "Default")
      (node (ref "IC4") (pin "3") (pinfunction "IN+_3") (pintype "input"))
      (node (ref "R43") (pin "1") (pinfunction "1_1") (pintype "passive"))
      (node (ref "R44") (pin "2") (pinfunction "2_2") (pintype "passive"))
    )
    (net (code "34") (name "Net-(N-AMPA-IN-)") (class "Default")
      (node (ref "C1") (pin "1") (pinfunction "1_1") (pintype "passive"))
      (node (ref "N-AMP") (pin "2") (pinfunction "IN-_2") (pintype "input"))
      (node (ref "N-PD1") (pin "2") (pinfunction "-_2") (pintype "bidirectional"))
      (node (ref "R1") (pin "1") (pinfunction "1_1") (pintype "passive"))
    )
    (net (code "35") (name "Net-(N-AMPA-OUT)") (class "Default")
      (node (ref "C1") (pin "2") (pinfunction "2_2") (pintype "passive"))
      (node (ref "C2") (pin "1") (pinfunction "1_1") (pintype "passive"))
      (node (ref "N-AMP") (pin "1") (pinfunction "OUT_1") (pintype "output"))
      (node (ref "R1") (pin "2") (pinfunction "2_2") (pintype "passive"))
    )
    (net (code "36") (name "Net-(N-AMPB-IN-)") (class "Default")
      (node (ref "C3") (pin "1") (pinfunction "1_1") (pintype "passive"))
      (node (ref "N-AMP") (pin "6") (pinfunction "IN-_6") (pintype "input"))
      (node (ref "R2") (pin "1") (pinfunction "1_1") (pintype "passive"))
      (node (ref "R4") (pin "1") (pinfunction "1_1") (pintype "passive"))
    )
    (net (code "37") (name "Net-(N-AMPB-OUT)") (class "Default")
      (node (ref "C3") (pin "2") (pinfunction "2_2") (pintype "passive"))
      (node (ref "C4") (pin "1") (pinfunction "1_1") (pintype "passive"))
      (node (ref "N-AMP") (pin "7") (pinfunction "OUT_7") (pintype "output"))
      (node (ref "R4") (pin "2") (pinfunction "2_2") (pintype "passive"))
    )
    (net (code "38") (name "Net-(N-AMPC-IN-)") (class "Default")
      (node (ref "C5") (pin "1") (pinfunction "1_1") (pintype "passive"))
      (node (ref "N-AMP") (pin "9") (pinfunction "IN-_9") (pintype "input"))
      (node (ref "R6") (pin "1") (pinfunction "1_1") (pintype "passive"))
      (node (ref "R7") (pin "1") (pinfunction "1_1") (pintype "passive"))
    )
    (net (code "39") (name "Net-(N-AMPC-OUT)") (class "Default")
      (node (ref "C33") (pin "1") (pinfunction "1_1") (pintype "passive"))
      (node (ref "C5") (pin "2") (pinfunction "2_2") (pintype "passive"))
      (node (ref "N-AMP") (pin "8") (pinfunction "OUT_8") (pintype "output"))
      (node (ref "R7") (pin "2") (pinfunction "2_2") (pintype "passive"))
    )
    (net (code "40") (name "Net-(N-AMPD-IN-)") (class "Default")
      (node (ref "C7") (pin "1") (pinfunction "1_1") (pintype "passive"))
      (node (ref "N-AMP") (pin "13") (pinfunction "IN-_13") (pintype "input"))
      (node (ref "R36") (pin "1") (pinfunction "1_1") (pintype "passive"))
      (node (ref "R8") (pin "1") (pinfunction "1_1") (pintype "passive"))
    )
    (net (code "41") (name "Net-(N-AMPD-OUT)") (class "Default")
      (node (ref "C7") (pin "2") (pinfunction "2_2") (pintype "passive"))
      (node (ref "D1") (pin "A") (pinfunction "A_A") (pintype "passive"))
      (node (ref "N-AMP") (pin "14") (pinfunction "OUT_14") (pintype "output"))
      (node (ref "R8") (pin "2") (pinfunction "2_2") (pintype "passive"))
    )
    (net (code "42") (name "Net-(ON-PadC)") (class "Default")
      (node (ref "ON") (pin "C") (pinfunction "C_C") (pintype "passive"))
      (node (ref "R19") (pin "2") (pinfunction "2_2") (pintype "passive"))
    )
    (net (code "43") (name "Net-(S-AMPA-IN-)") (class "Default")
      (node (ref "C8") (pin "1") (pinfunction "1_1") (pintype "passive"))
      (node (ref "R9") (pin "1") (pinfunction "1_1") (pintype "passive"))
      (node (ref "S-AMP") (pin "2") (pinfunction "IN-_2") (pintype "input"))
      (node (ref "S-PD1") (pin "2") (pinfunction "-_2") (pintype "bidirectional"))
    )
    (net (code "44") (name "Net-(S-AMPA-OUT)") (class "Default")
      (node (ref "C8") (pin "2") (pinfunction "2_2") (pintype "passive"))
      (node (ref "C9") (pin "1") (pinfunction "1_1") (pintype "passive"))
      (node (ref "R9") (pin "2") (pinfunction "2_2") (pintype "passive"))
      (node (ref "S-AMP") (pin "1") (pinfunction "OUT_1") (pintype "output"))
    )
    (net (code "45") (name "Net-(S-AMPB-IN-)") (class "Default")
      (node (ref "C10") (pin "1") (pinfunction "1_1") (pintype "passive"))
      (node (ref "R10") (pin "1") (pinfunction "1_1") (pintype "passive"))
      (node (ref "R12") (pin "1") (pinfunction "1_1") (pintype "passive"))
      (node (ref "S-AMP") (pin "6") (pinfunction "IN-_6") (pintype "input"))
    )
    (net (code "46") (name "Net-(S-AMPB-OUT)") (class "Default")
      (node (ref "C10") (pin "2") (pinfunction "2_2") (pintype "passive"))
      (node (ref "C11") (pin "1") (pinfunction "1_1") (pintype "passive"))
      (node (ref "R12") (pin "2") (pinfunction "2_2") (pintype "passive"))
      (node (ref "S-AMP") (pin "7") (pinfunction "OUT_7") (pintype "output"))
    )
    (net (code "47") (name "Net-(S-AMPC-IN-)") (class "Default")
      (node (ref "C12") (pin "1") (pinfunction "1_1") (pintype "passive"))
      (node (ref "R14") (pin "1") (pinfunction "1_1") (pintype "passive"))
      (node (ref "R15") (pin "1") (pinfunction "1_1") (pintype "passive"))
      (node (ref "S-AMP") (pin "9") (pinfunction "IN-_9") (pintype "input"))
    )
    (net (code "48") (name "Net-(S-AMPC-OUT)") (class "Default")
      (node (ref "C12") (pin "2") (pinfunction "2_2") (pintype "passive"))
      (node (ref "C34") (pin "1") (pinfunction "1_1") (pintype "passive"))
      (node (ref "R15") (pin "2") (pinfunction "2_2") (pintype "passive"))
      (node (ref "S-AMP") (pin "8") (pinfunction "OUT_8") (pintype "output"))
    )
    (net (code "49") (name "Net-(S-AMPD-IN-)") (class "Default")
      (node (ref "C14") (pin "1") (pinfunction "1_1") (pintype "passive"))
      (node (ref "R16") (pin "1") (pinfunction "1_1") (pintype "passive"))
      (node (ref "R38") (pin "1") (pinfunction "1_1") (pintype "passive"))
      (node (ref "S-AMP") (pin "13") (pinfunction "IN-_13") (pintype "input"))
    )
    (net (code "50") (name "Net-(W-AMPA-IN-)") (class "Default")
      (node (ref "C22") (pin "1") (pinfunction "1_1") (pintype "passive"))
      (node (ref "R25") (pin "1") (pinfunction "1_1") (pintype "passive"))
      (node (ref "W-AMP") (pin "2") (pinfunction "IN-_2") (pintype "input"))
      (node (ref "W-PD1") (pin "2") (pinfunction "-_2") (pintype "bidirectional"))
    )
    (net (code "51") (name "Net-(W-AMPA-OUT)") (class "Default")
      (node (ref "C22") (pin "2") (pinfunction "2_2") (pintype "passive"))
      (node (ref "C23") (pin "1") (pinfunction "1_1") (pintype "passive"))
      (node (ref "R25") (pin "2") (pinfunction "2_2") (pintype "passive"))
      (node (ref "W-AMP") (pin "1") (pinfunction "OUT_1") (pintype "output"))
    )
    (net (code "52") (name "Net-(W-AMPB-IN-)") (class "Default")
      (node (ref "C24") (pin "1") (pinfunction "1_1") (pintype "passive"))
      (node (ref "R26") (pin "1") (pinfunction "1_1") (pintype "passive"))
      (node (ref "R28") (pin "1") (pinfunction "1_1") (pintype "passive"))
      (node (ref "W-AMP") (pin "6") (pinfunction "IN-_6") (pintype "input"))
    )
    (net (code "53") (name "Net-(W-AMPB-OUT)") (class "Default")
      (node (ref "C24") (pin "2") (pinfunction "2_2") (pintype "passive"))
      (node (ref "C25") (pin "1") (pinfunction "1_1") (pintype "passive"))
      (node (ref "R28") (pin "2") (pinfunction "2_2") (pintype "passive"))
      (node (ref "W-AMP") (pin "7") (pinfunction "OUT_7") (pintype "output"))
    )
    (net (code "54") (name "Net-(W-AMPC-IN-)") (class "Default")
      (node (ref "C26") (pin "1") (pinfunction "1_1") (pintype "passive"))
      (node (ref "R30") (pin "1") (pinfunction "1_1") (pintype "passive"))
      (node (ref "R31") (pin "1") (pinfunction "1_1") (pintype "passive"))
      (node (ref "W-AMP") (pin "9") (pinfunction "IN-_9") (pintype "input"))
    )
    (net (code "55") (name "Net-(W-AMPC-OUT)") (class "Default")
      (node (ref "C26") (pin "2") (pinfunction "2_2") (pintype "passive"))
      (node (ref "C36") (pin "1") (pinfunction "1_1") (pintype "passive"))
      (node (ref "R31") (pin "2") (pinfunction "2_2") (pintype "passive"))
      (node (ref "W-AMP") (pin "8") (pinfunction "OUT_8") (pintype "output"))
    )
    (net (code "56") (name "Net-(W-AMPD-IN-)") (class "Default")
      (node (ref "C28") (pin "1") (pinfunction "1_1") (pintype "passive"))
      (node (ref "R32") (pin "1") (pinfunction "1_1") (pintype "passive"))
      (node (ref "R48") (pin "1") (pinfunction "1_1") (pintype "passive"))
      (node (ref "W-AMP") (pin "13") (pinfunction "IN-_13") (pintype "input"))
    )
    (net (code "57") (name "Net-(W-AMPD-OUT)") (class "Default")
      (node (ref "C28") (pin "2") (pinfunction "2_2") (pintype "passive"))
      (node (ref "D4") (pin "A") (pinfunction "A_A") (pintype "passive"))
      (node (ref "R32") (pin "2") (pinfunction "2_2") (pintype "passive"))
      (node (ref "W-AMP") (pin "14") (pinfunction "OUT_14") (pintype "output"))
    )
    (net (code "58") (name "S-OUT") (class "Default")
      (node (ref "C13") (pin "2") (pinfunction "2_2") (pintype "passive"))
      (node (ref "D2") (pin "C") (pinfunction "C_C") (pintype "passive"))
      (node (ref "JP2") (pin "4") (pinfunction "4_4") (pintype "passive"))
      (node (ref "R5") (pin "2") (pinfunction "2_2") (pintype "passive"))
    )
    (net (code "59") (name "W-OUT") (class "Default")
      (node (ref "C27") (pin "2") (pinfunction "2_2") (pintype "passive"))
      (node (ref "D4") (pin "C") (pinfunction "C_C") (pintype "passive"))
      (node (ref "JP2") (pin "5") (pinfunction "5_5") (pintype "passive"))
      (node (ref "R13") (pin "2") (pinfunction "2_2") (pintype "passive"))
    )
  )
)
